# SCH_PoC_Interrupt_Jao.net
KiCad netlist of a schematic drawn in EasyEDA
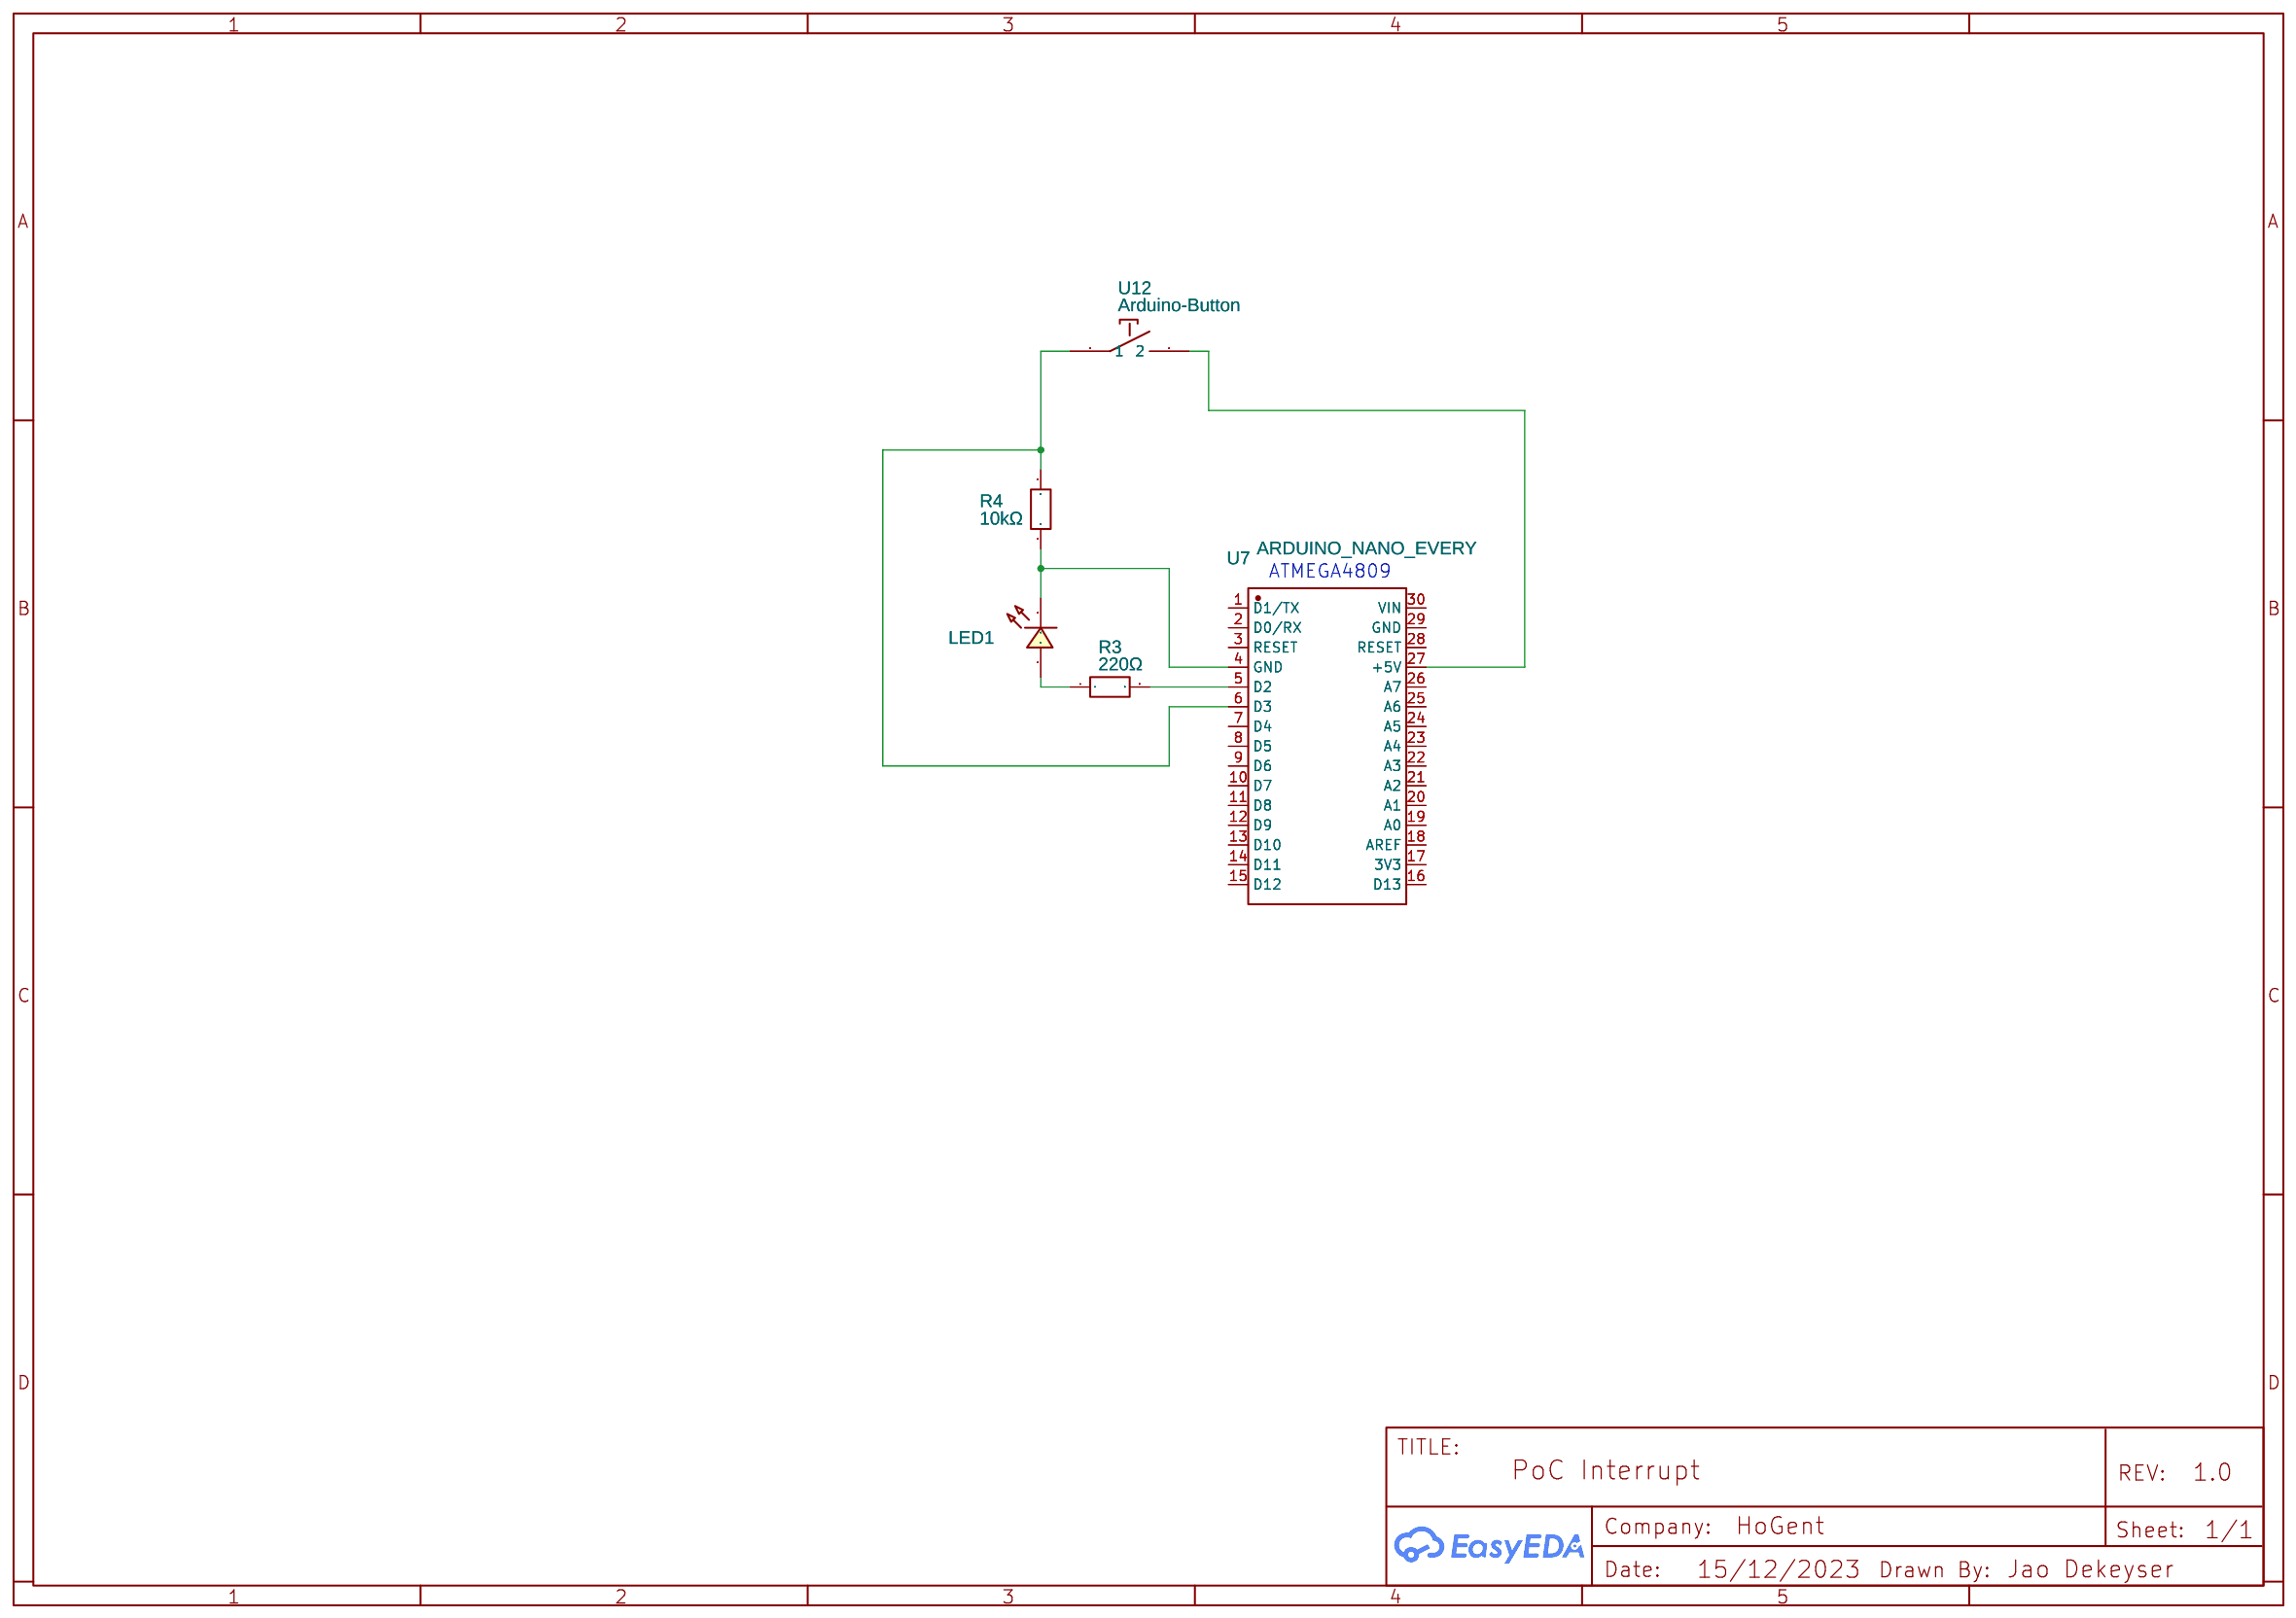
[diagram p0: schematic sheet]

(export (version "E")
  (design (tool "Eeschema 10.0.6"))
  (components
    (comp (ref "LED1")
      (value "LED-TH-5mm_R")
      (fields
        (field (name "Manufacturer Part") "333-2SURD/S530-A3")
        (field (name "Manufacturer") "EVERLIGHT(台湾亿光)")
      )
      (libsource (lib "") (part "LED-TH-5mm_R"))
    )
    (comp (ref "R3")
      (value "220Ω")
      (libsource (lib "") (part "AXIAL RESISTOR 220 OHM - TH_BD2.3-L6.0-P10.00-D0.4_1"))
    )
    (comp (ref "R4")
      (value "10kΩ")
      (libsource (lib "") (part "AXIAL RESISTOR 220 OHM - TH_BD2.3-L6.0-P10.00-D0.4"))
    )
    (comp (ref "U7")
      (value "ARDUINO_NANO_EVERY")
      (fields (field (name "Manufacturer Part") "ARDUINO_NANO"))
      (libsource (lib "") (part "ARDUINO_NANO"))
    )
    (comp (ref "U12")
      (value "Arduino-Button")
      (fields (field (name "Manufacturer Part") "SW100664"))
      (libsource (lib "") (part "Arduino-Button"))
    )
  )
  (nets
    (net (code "1") (name "Net-(LED1-Pad1)") (class "Default")
      (node (ref "LED1") (pin "1") (pinfunction "1_1") (pintype "unspecified"))
      (node (ref "R3") (pin "1") (pinfunction "1_1") (pintype "unspecified"))
    )
    (net (code "2") (name "Net-(LED1-Pad2)") (class "Default")
      (node (ref "LED1") (pin "2") (pinfunction "2_2") (pintype "unspecified"))
      (node (ref "R4") (pin "1") (pinfunction "1_1") (pintype "unspecified"))
      (node (ref "U7") (pin "4") (pinfunction "GND_4") (pintype "unspecified"))
    )
    (net (code "3") (name "Net-(U7-+5V)") (class "Default")
      (node (ref "U12") (pin "2") (pinfunction "2_2") (pintype "unspecified"))
      (node (ref "U7") (pin "27") (pinfunction "+5V_27") (pintype "unspecified"))
    )
    (net (code "4") (name "Net-(U7-D2)") (class "Default")
      (node (ref "R3") (pin "2") (pinfunction "2_2") (pintype "unspecified"))
      (node (ref "U7") (pin "5") (pinfunction "D2_5") (pintype "unspecified"))
    )
    (net (code "5") (name "Net-(U7-D3)") (class "Default")
      (node (ref "R4") (pin "2") (pinfunction "2_2") (pintype "unspecified"))
      (node (ref "U12") (pin "1") (pinfunction "1_1") (pintype "unspecified"))
      (node (ref "U7") (pin "6") (pinfunction "D3_6") (pintype "unspecified"))
    )
    (net (code "6") (name "unconnected-(U7-3V3-Pad17)") (class "Default")
      (node (ref "U7") (pin "17") (pinfunction "3V3_17") (pintype "unspecified"))
    )
    (net (code "7") (name "unconnected-(U7-A0-Pad19)") (class "Default")
      (node (ref "U7") (pin "19") (pinfunction "A0_19") (pintype "unspecified"))
    )
    (net (code "8") (name "unconnected-(U7-A1-Pad20)") (class "Default")
      (node (ref "U7") (pin "20") (pinfunction "A1_20") (pintype "unspecified"))
    )
    (net (code "9") (name "unconnected-(U7-A2-Pad21)") (class "Default")
      (node (ref "U7") (pin "21") (pinfunction "A2_21") (pintype "unspecified"))
    )
    (net (code "10") (name "unconnected-(U7-A3-Pad22)") (class "Default")
      (node (ref "U7") (pin "22") (pinfunction "A3_22") (pintype "unspecified"))
    )
    (net (code "11") (name "unconnected-(U7-A4-Pad23)") (class "Default")
      (node (ref "U7") (pin "23") (pinfunction "A4_23") (pintype "unspecified"))
    )
    (net (code "12") (name "unconnected-(U7-A5-Pad24)") (class "Default")
      (node (ref "U7") (pin "24") (pinfunction "A5_24") (pintype "unspecified"))
    )
    (net (code "13") (name "unconnected-(U7-A6-Pad25)") (class "Default")
      (node (ref "U7") (pin "25") (pinfunction "A6_25") (pintype "unspecified"))
    )
    (net (code "14") (name "unconnected-(U7-A7-Pad26)") (class "Default")
      (node (ref "U7") (pin "26") (pinfunction "A7_26") (pintype "unspecified"))
    )
    (net (code "15") (name "unconnected-(U7-AREF-Pad18)") (class "Default")
      (node (ref "U7") (pin "18") (pinfunction "AREF_18") (pintype "unspecified"))
    )
    (net (code "16") (name "unconnected-(U7-D0{slash}RX-Pad2)") (class "Default")
      (node (ref "U7") (pin "2") (pinfunction "D0/RX_2") (pintype "unspecified"))
    )
    (net (code "17") (name "unconnected-(U7-D1{slash}TX-Pad1)") (class "Default")
      (node (ref "U7") (pin "1") (pinfunction "D1/TX_1") (pintype "unspecified"))
    )
    (net (code "18") (name "unconnected-(U7-D4-Pad7)") (class "Default")
      (node (ref "U7") (pin "7") (pinfunction "D4_7") (pintype "unspecified"))
    )
    (net (code "19") (name "unconnected-(U7-D5-Pad8)") (class "Default")
      (node (ref "U7") (pin "8") (pinfunction "D5_8") (pintype "unspecified"))
    )
    (net (code "20") (name "unconnected-(U7-D6-Pad9)") (class "Default")
      (node (ref "U7") (pin "9") (pinfunction "D6_9") (pintype "unspecified"))
    )
    (net (code "21") (name "unconnected-(U7-D7-Pad10)") (class "Default")
      (node (ref "U7") (pin "10") (pinfunction "D7_10") (pintype "unspecified"))
    )
    (net (code "22") (name "unconnected-(U7-D8-Pad11)") (class "Default")
      (node (ref "U7") (pin "11") (pinfunction "D8_11") (pintype "unspecified"))
    )
    (net (code "23") (name "unconnected-(U7-D9-Pad12)") (class "Default")
      (node (ref "U7") (pin "12") (pinfunction "D9_12") (pintype "unspecified"))
    )
    (net (code "24") (name "unconnected-(U7-D10-Pad13)") (class "Default")
      (node (ref "U7") (pin "13") (pinfunction "D10_13") (pintype "unspecified"))
    )
    (net (code "25") (name "unconnected-(U7-D11-Pad14)") (class "Default")
      (node (ref "U7") (pin "14") (pinfunction "D11_14") (pintype "unspecified"))
    )
    (net (code "26") (name "unconnected-(U7-D12-Pad15)") (class "Default")
      (node (ref "U7") (pin "15") (pinfunction "D12_15") (pintype "unspecified"))
    )
    (net (code "27") (name "unconnected-(U7-D13-Pad16)") (class "Default")
      (node (ref "U7") (pin "16") (pinfunction "D13_16") (pintype "unspecified"))
    )
    (net (code "28") (name "unconnected-(U7-GND-Pad29)") (class "Default")
      (node (ref "U7") (pin "29") (pinfunction "GND_29") (pintype "unspecified"))
    )
    (net (code "29") (name "unconnected-(U7-RESET-Pad3)") (class "Default")
      (node (ref "U7") (pin "3") (pinfunction "RESET_3") (pintype "unspecified"))
    )
    (net (code "30") (name "unconnected-(U7-RESET-Pad28)") (class "Default")
      (node (ref "U7") (pin "28") (pinfunction "RESET_28") (pintype "unspecified"))
    )
    (net (code "31") (name "unconnected-(U7-VIN-Pad30)") (class "Default")
      (node (ref "U7") (pin "30") (pinfunction "VIN_30") (pintype "unspecified"))
    )
  )
)
